# bmx160-breakout.net
KiCad netlist of a schematic drawn in EAGLE
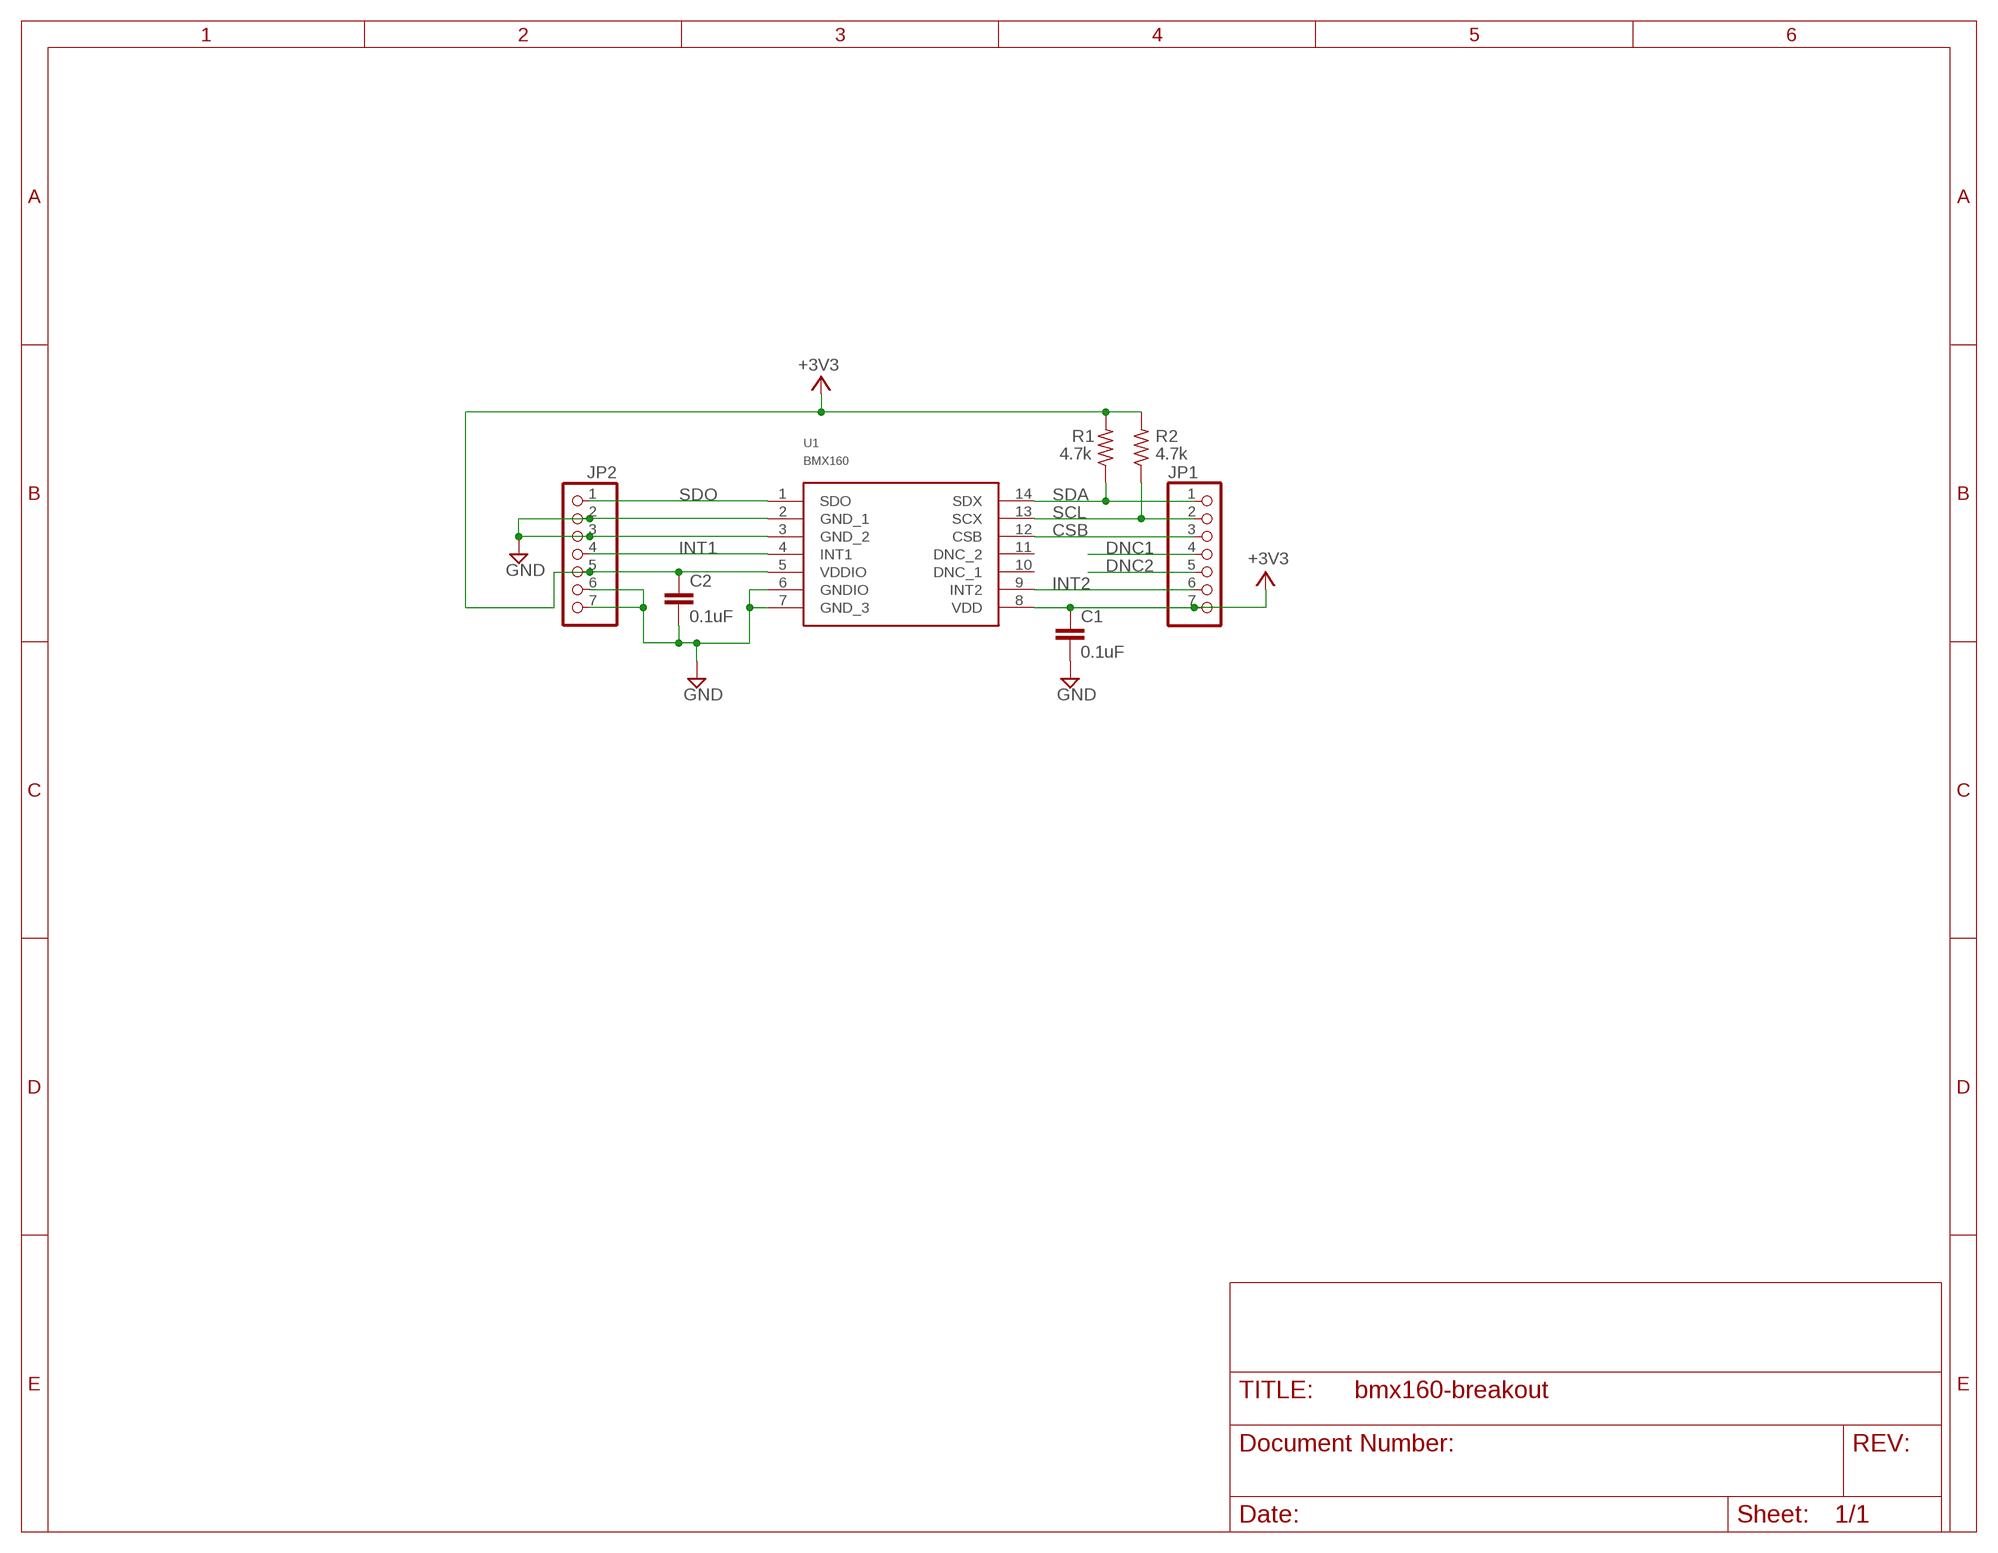
[diagram p0: schematic, sheet 1]

(export (version "E")
  (design (tool "Eeschema 10.0.6"))
  (components
    (comp (ref "C1")
      (value "0.1uF")
      (footprint "eagle-import:C0805")
      (libsource (lib "eagle-import") (part "C-EUC0805"))
    )
    (comp (ref "C2")
      (value "0.1uF")
      (footprint "eagle-import:C0805")
      (libsource (lib "eagle-import") (part "C-EUC0805"))
    )
    (comp (ref "JP1")
      (value "PINHD-1X7")
      (footprint "eagle-import:1X07")
      (libsource (lib "eagle-import") (part "PINHD-1X7"))
    )
    (comp (ref "JP2")
      (value "PINHD-1X7ALL_ROUND")
      (footprint "eagle-import:1X07_")
      (libsource (lib "eagle-import") (part "PINHD-1X7ALL_ROUND"))
    )
    (comp (ref "R1")
      (value "4.7k")
      (footprint "eagle-import:R0805")
      (libsource (lib "eagle-import") (part "R-US_R0805"))
    )
    (comp (ref "R2")
      (value "4.7k")
      (footprint "eagle-import:R0805")
      (libsource (lib "eagle-import") (part "R-US_R0805"))
    )
    (comp (ref "U1")
      (value "BMX160")
      (footprint "eagle-import:QFN14P50_300X250X100L47X25N")
      (libsource (lib "eagle-import") (part "BMX160"))
    )
  )
  (nets
    (net (code "1") (name "+3V3") (class "Default")
      (node (ref "C1") (pin "1") (pinfunction "1_1") (pintype "passive"))
      (node (ref "C2") (pin "1") (pinfunction "1_1") (pintype "passive"))
      (node (ref "JP1") (pin "7") (pinfunction "7_7") (pintype "passive"))
      (node (ref "JP2") (pin "5") (pinfunction "5_5") (pintype "passive"))
      (node (ref "R1") (pin "2") (pinfunction "2_2") (pintype "passive"))
      (node (ref "R2") (pin "2") (pinfunction "2_2") (pintype "passive"))
      (node (ref "U1") (pin "5") (pinfunction "VDDIO_5") (pintype "bidirectional"))
      (node (ref "U1") (pin "8") (pinfunction "VDD_8") (pintype "bidirectional"))
    )
    (net (code "2") (name "/CSB") (class "Default")
      (node (ref "JP1") (pin "3") (pinfunction "3_3") (pintype "passive"))
      (node (ref "U1") (pin "12") (pinfunction "CSB_12") (pintype "bidirectional"))
    )
    (net (code "3") (name "/DNC1") (class "Default")
      (node (ref "JP1") (pin "4") (pinfunction "4_4") (pintype "passive"))
    )
    (net (code "4") (name "/DNC2") (class "Default")
      (node (ref "JP1") (pin "5") (pinfunction "5_5") (pintype "passive"))
    )
    (net (code "5") (name "/INT1") (class "Default")
      (node (ref "JP2") (pin "4") (pinfunction "4_4") (pintype "passive"))
      (node (ref "U1") (pin "4") (pinfunction "INT1_4") (pintype "bidirectional"))
    )
    (net (code "6") (name "/INT2") (class "Default")
      (node (ref "JP1") (pin "6") (pinfunction "6_6") (pintype "passive"))
      (node (ref "U1") (pin "9") (pinfunction "INT2_9") (pintype "bidirectional"))
    )
    (net (code "7") (name "/SCL") (class "Default")
      (node (ref "JP1") (pin "2") (pinfunction "2_2") (pintype "passive"))
      (node (ref "R2") (pin "1") (pinfunction "1_1") (pintype "passive"))
      (node (ref "U1") (pin "13") (pinfunction "SCX_13") (pintype "bidirectional"))
    )
    (net (code "8") (name "/SDA") (class "Default")
      (node (ref "JP1") (pin "1") (pinfunction "1_1") (pintype "passive"))
      (node (ref "R1") (pin "1") (pinfunction "1_1") (pintype "passive"))
      (node (ref "U1") (pin "14") (pinfunction "SDX_14") (pintype "bidirectional"))
    )
    (net (code "9") (name "/SDO") (class "Default")
      (node (ref "JP2") (pin "1") (pinfunction "1_1") (pintype "passive"))
      (node (ref "U1") (pin "1") (pinfunction "SDO_1") (pintype "bidirectional"))
    )
    (net (code "10") (name "GND") (class "Default")
      (node (ref "C1") (pin "2") (pinfunction "2_2") (pintype "passive"))
      (node (ref "C2") (pin "2") (pinfunction "2_2") (pintype "passive"))
      (node (ref "JP2") (pin "2") (pinfunction "2_2") (pintype "passive"))
      (node (ref "JP2") (pin "3") (pinfunction "3_3") (pintype "passive"))
      (node (ref "JP2") (pin "6") (pinfunction "6_6") (pintype "passive"))
      (node (ref "JP2") (pin "7") (pinfunction "7_7") (pintype "passive"))
      (node (ref "U1") (pin "2") (pinfunction "GND_1_2") (pintype "bidirectional"))
      (node (ref "U1") (pin "3") (pinfunction "GND_2_3") (pintype "bidirectional"))
      (node (ref "U1") (pin "6") (pinfunction "GNDIO_6") (pintype "bidirectional"))
      (node (ref "U1") (pin "7") (pinfunction "GND_3_7") (pintype "bidirectional"))
    )
    (net (code "11") (name "unconnected-(U1-DNC_1-Pad10)") (class "Default")
      (node (ref "U1") (pin "10") (pinfunction "DNC_1_10") (pintype "bidirectional"))
    )
    (net (code "12") (name "unconnected-(U1-DNC_2-Pad11)") (class "Default")
      (node (ref "U1") (pin "11") (pinfunction "DNC_2_11") (pintype "bidirectional"))
    )
  )
)
